# water_level_sc.net
KiCad netlist of a schematic drawn in EAGLE
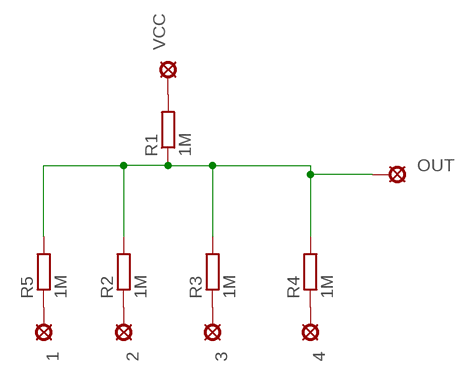
[diagram p0: schematic, sheet 1]

(export (version "E")
  (design (tool "Eeschema 10.0.6"))
  (components
    (comp (ref "1")
      (value "SE13")
      (footprint "eagle-import:SE13")
      (libsource (lib "eagle-import") (part "SE13"))
    )
    (comp (ref "2")
      (value "SE13")
      (footprint "eagle-import:SE13")
      (libsource (lib "eagle-import") (part "SE13"))
    )
    (comp (ref "3")
      (value "SE13")
      (footprint "eagle-import:SE13")
      (libsource (lib "eagle-import") (part "SE13"))
    )
    (comp (ref "4")
      (value "SE13")
      (footprint "eagle-import:SE13")
      (libsource (lib "eagle-import") (part "SE13"))
    )
    (comp (ref "OUT")
      (value "SE13")
      (footprint "eagle-import:SE13")
      (libsource (lib "eagle-import") (part "SE13"))
    )
    (comp (ref "R1")
      (value "1M")
      (footprint "eagle-import:R0805")
      (libsource (lib "eagle-import") (part "R-EU_R0805"))
    )
    (comp (ref "R2")
      (value "1M")
      (footprint "eagle-import:R0805")
      (libsource (lib "eagle-import") (part "R-EU_R0805"))
    )
    (comp (ref "R3")
      (value "1M")
      (footprint "eagle-import:R0805")
      (libsource (lib "eagle-import") (part "R-EU_R0805"))
    )
    (comp (ref "R4")
      (value "1M")
      (footprint "eagle-import:R0805")
      (libsource (lib "eagle-import") (part "R-EU_R0805"))
    )
    (comp (ref "R5")
      (value "1M")
      (footprint "eagle-import:R0805")
      (libsource (lib "eagle-import") (part "R-EU_R0805"))
    )
    (comp (ref "VCC")
      (value "SE13")
      (footprint "eagle-import:SE13")
      (libsource (lib "eagle-import") (part "SE13"))
    )
  )
  (nets
    (net (code "1") (name "Net-(1-PadMP)") (class "Default")
      (node (ref "1") (pin "MP") (pinfunction "MP_MP") (pintype "passive"))
      (node (ref "R5") (pin "1") (pinfunction "1_1") (pintype "passive"))
    )
    (net (code "2") (name "Net-(2-PadMP)") (class "Default")
      (node (ref "2") (pin "MP") (pinfunction "MP_MP") (pintype "passive"))
      (node (ref "R2") (pin "1") (pinfunction "1_1") (pintype "passive"))
    )
    (net (code "3") (name "Net-(3-PadMP)") (class "Default")
      (node (ref "3") (pin "MP") (pinfunction "MP_MP") (pintype "passive"))
      (node (ref "R3") (pin "1") (pinfunction "1_1") (pintype "passive"))
    )
    (net (code "4") (name "Net-(4-PadMP)") (class "Default")
      (node (ref "4") (pin "MP") (pinfunction "MP_MP") (pintype "passive"))
      (node (ref "R4") (pin "1") (pinfunction "1_1") (pintype "passive"))
    )
    (net (code "5") (name "Net-(OUT-PadMP)") (class "Default")
      (node (ref "OUT") (pin "MP") (pinfunction "MP_MP") (pintype "passive"))
      (node (ref "R1") (pin "1") (pinfunction "1_1") (pintype "passive"))
      (node (ref "R2") (pin "2") (pinfunction "2_2") (pintype "passive"))
      (node (ref "R3") (pin "2") (pinfunction "2_2") (pintype "passive"))
      (node (ref "R4") (pin "2") (pinfunction "2_2") (pintype "passive"))
      (node (ref "R5") (pin "2") (pinfunction "2_2") (pintype "passive"))
    )
    (net (code "6") (name "Net-(R1-Pad2)") (class "Default")
      (node (ref "R1") (pin "2") (pinfunction "2_2") (pintype "passive"))
      (node (ref "VCC") (pin "MP") (pinfunction "MP_MP") (pintype "passive"))
    )
  )
)
